# DAC.net
KiCad netlist of a schematic drawn in Altium Designer
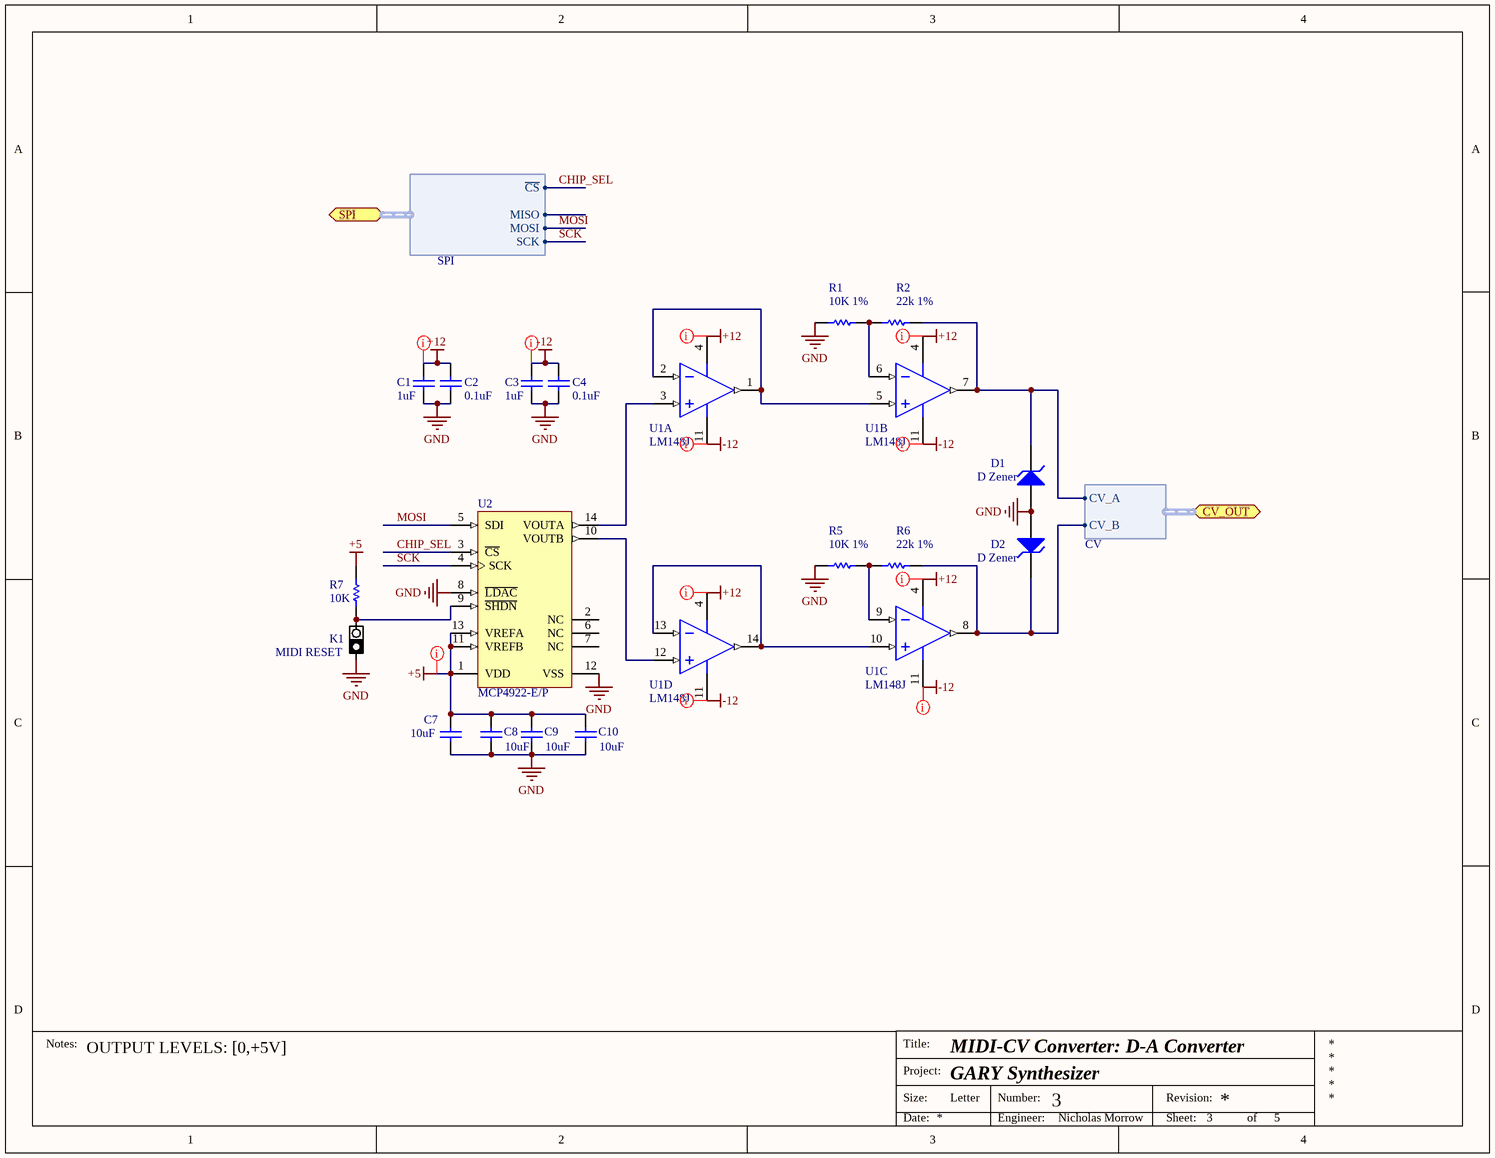
[diagram p0: DAC.SchDoc]

(export (version "E")
  (design (tool "Eeschema 10.0.6"))
  (components
    (comp (ref "C1")
      (value "1uF")
      (footprint "CAP 5X11")
      (description "Capacitor")
      (fields (field (name "Comment") "Cap") (field (name "PUBLISHER") "Altium Limited"))
      (libsource (lib "Miscellaneous Devices") (part "Cap"))
    )
    (comp (ref "C2")
      (value "0.1uF")
      (footprint "CAP 5X11")
      (description "Capacitor")
      (fields (field (name "Comment") "Cap") (field (name "PUBLISHER") "Altium Limited"))
      (libsource (lib "Miscellaneous Devices") (part "Cap"))
    )
    (comp (ref "C3")
      (value "1uF")
      (footprint "CAP 5X11")
      (description "Capacitor")
      (fields (field (name "Comment") "Cap") (field (name "PUBLISHER") "Altium Limited"))
      (libsource (lib "Miscellaneous Devices") (part "Cap"))
    )
    (comp (ref "C4")
      (value "0.1uF")
      (footprint "CAP 5X11")
      (description "Capacitor")
      (fields (field (name "Comment") "Cap") (field (name "PUBLISHER") "Altium Limited"))
      (libsource (lib "Miscellaneous Devices") (part "Cap"))
    )
    (comp (ref "C7")
      (value "10uF")
      (footprint "CAP 5X11")
      (description "Capacitor")
      (fields (field (name "Comment") "Cap") (field (name "PUBLISHER") "Altium Limited"))
      (libsource (lib "Miscellaneous Devices") (part "Cap"))
    )
    (comp (ref "C8")
      (value "10uF")
      (footprint "CAP 5X11")
      (description "Capacitor")
      (fields (field (name "Comment") "Cap") (field (name "PUBLISHER") "Altium Limited"))
      (libsource (lib "Miscellaneous Devices") (part "Cap"))
    )
    (comp (ref "C9")
      (value "10uF")
      (footprint "CAP 5X11")
      (description "Capacitor")
      (fields (field (name "Comment") "Cap") (field (name "PUBLISHER") "Altium Limited"))
      (libsource (lib "Miscellaneous Devices") (part "Cap"))
    )
    (comp (ref "C10")
      (value "10uF")
      (footprint "CAP 5X11")
      (description "Capacitor")
      (fields (field (name "Comment") "Cap") (field (name "PUBLISHER") "Altium Limited"))
      (libsource (lib "Miscellaneous Devices") (part "Cap"))
    )
    (comp (ref "D1")
      (value "D Zener")
      (footprint "DIODE-0.4")
      (description "Zener Diode")
      (fields
        (field (name "MANUFACTURER") "NXP Semiconductors")
        (field (name "MANUFACTURER PART NUMBER") "NZX3V0C,133")
        (field (name "PUBLISHER") "Altium Limited")
      )
      (libsource (lib "Miscellaneous Devices") (part "D Zener"))
    )
    (comp (ref "D2")
      (value "D Zener")
      (footprint "DIODE-0.4")
      (description "Zener Diode")
      (fields
        (field (name "MANUFACTURER") "NXP Semiconductors")
        (field (name "MANUFACTURER PART NUMBER") "NZX3V0C,133")
        (field (name "PUBLISHER") "Altium Limited")
      )
      (libsource (lib "Miscellaneous Devices") (part "D Zener"))
    )
    (comp (ref "K1")
      (value "MIDI RESET")
      (footprint "JMPR2")
      (description "JMPR2 OPEN BY DEFAULT")
      (fields
        (field (name "MANUFACTURER") "Sullins Connector Solutions")
        (field (name "MANUFACTURER PART NUMBER") "PBC36SAAN")
      )
      (libsource (lib "vh_altium_library") (part "JMPR2"))
    )
    (comp (ref "R1")
      (value "10K 1%")
      (footprint "AXIAL-0.3")
      (description "Resistor")
      (fields (field (name "PUBLISHER") "Altium Limited"))
      (libsource (lib "Miscellaneous Devices") (part "Res1"))
    )
    (comp (ref "R2")
      (value "22k 1%")
      (footprint "AXIAL-0.3")
      (description "Resistor")
      (fields (field (name "PUBLISHER") "Altium Limited"))
      (libsource (lib "Miscellaneous Devices") (part "Res1"))
    )
    (comp (ref "R5")
      (value "10K 1%")
      (footprint "AXIAL-0.3")
      (description "Resistor")
      (fields (field (name "PUBLISHER") "Altium Limited"))
      (libsource (lib "Miscellaneous Devices") (part "Res1"))
    )
    (comp (ref "R6")
      (value "22k 1%")
      (footprint "AXIAL-0.3")
      (description "Resistor")
      (fields (field (name "PUBLISHER") "Altium Limited"))
      (libsource (lib "Miscellaneous Devices") (part "Res1"))
    )
    (comp (ref "R7")
      (value "10K")
      (footprint "AXIAL-0.3")
      (description "Resistor")
      (fields (field (name "PUBLISHER") "Altium Limited"))
      (libsource (lib "Miscellaneous Devices") (part "Res1"))
    )
    (comp (ref "U1")
      (value "LM148J")
      (footprint "J14A")
      (description "Series Quad 741 Op Amp, 14-pin CerDIP")
      (fields (field (name "MANUFACTURER") "National Semiconductor"))
      (libsource (lib "National Semiconductor Amplifier") (part "LM148J"))
    )
    (comp (ref "U2")
      (value "MCP4922-E/P")
      (footprint "PDIP300-P14")
      (description "12-Bit DAC with SPI Interface, 14-Pin PDIP, Extended Temperature")
      (fields (field (name "MANUFACTURER") "Microchip"))
      (libsource (lib "Microchip Mixed Signal") (part "MCP4922-E/P"))
    )
  )
  (nets
    (net (code "3") (name "+5") (class "Default")
      (node (ref "C10") (pin "2") (pinfunction "2_2") (pintype "passive"))
      (node (ref "C7") (pin "2") (pinfunction "2_2") (pintype "passive"))
      (node (ref "C8") (pin "2") (pinfunction "2_2") (pintype "passive"))
      (node (ref "C9") (pin "2") (pinfunction "2_2") (pintype "passive"))
      (node (ref "R7") (pin "2") (pinfunction "2_2") (pintype "passive"))
      (node (ref "U2") (pin "1") (pinfunction "VDD_1") (pintype "power_in"))
      (node (ref "U2") (pin "11") (pinfunction "VREFB_11") (pintype "input"))
      (node (ref "U2") (pin "13") (pinfunction "VREFA_13") (pintype "input"))
    )
    (net (code "4") (name "+12") (class "Default")
      (node (ref "C1") (pin "2") (pinfunction "2_2") (pintype "passive"))
      (node (ref "C2") (pin "2") (pinfunction "2_2") (pintype "passive"))
      (node (ref "U1") (pin "4") (pinfunction "V+_4") (pintype "power_in"))
    )
    (net (code "5") (name "-12") (class "Default")
      (node (ref "C3") (pin "2") (pinfunction "2_2") (pintype "passive"))
      (node (ref "C4") (pin "2") (pinfunction "2_2") (pintype "passive"))
      (node (ref "U1") (pin "11") (pinfunction "V-_11") (pintype "power_in"))
    )
    (net (code "6") (name "/CHIP_SEL") (class "Default")
      (node (ref "U2") (pin "3") (pinfunction "~{CS}_3") (pintype "input"))
    )
    (net (code "7") (name "/MOSI") (class "Default")
      (node (ref "U2") (pin "5") (pinfunction "SDI_5") (pintype "input"))
    )
    (net (code "8") (name "/SCK") (class "Default")
      (node (ref "U2") (pin "4") (pinfunction "SCK_4") (pintype "input"))
    )
    (net (code "11") (name "GND") (class "Default")
      (node (ref "C1") (pin "1") (pinfunction "1_1") (pintype "passive"))
      (node (ref "C10") (pin "1") (pinfunction "1_1") (pintype "passive"))
      (node (ref "C2") (pin "1") (pinfunction "1_1") (pintype "passive"))
      (node (ref "C3") (pin "1") (pinfunction "1_1") (pintype "passive"))
      (node (ref "C4") (pin "1") (pinfunction "1_1") (pintype "passive"))
      (node (ref "C7") (pin "1") (pinfunction "1_1") (pintype "passive"))
      (node (ref "C8") (pin "1") (pinfunction "1_1") (pintype "passive"))
      (node (ref "C9") (pin "1") (pinfunction "1_1") (pintype "passive"))
      (node (ref "D1") (pin "1") (pinfunction "A_1") (pintype "passive"))
      (node (ref "D2") (pin "1") (pinfunction "A_1") (pintype "passive"))
      (node (ref "K1") (pin "1") (pintype "passive"))
      (node (ref "R1") (pin "2") (pinfunction "2_2") (pintype "passive"))
      (node (ref "R5") (pin "2") (pinfunction "2_2") (pintype "passive"))
      (node (ref "U2") (pin "12") (pinfunction "VSS_12") (pintype "power_in"))
      (node (ref "U2") (pin "8") (pinfunction "~{LDAC}_8") (pintype "input"))
    )
    (net (code "12") (name "Net-(D1-K)") (class "Default")
      (node (ref "D1") (pin "2") (pinfunction "K_2") (pintype "passive"))
      (node (ref "R2") (pin "1") (pinfunction "1_1") (pintype "passive"))
      (node (ref "U1") (pin "7") (pinfunction "OUT2_7") (pintype "output"))
    )
    (net (code "13") (name "Net-(D2-K)") (class "Default")
      (node (ref "D2") (pin "2") (pinfunction "K_2") (pintype "passive"))
      (node (ref "R6") (pin "1") (pinfunction "1_1") (pintype "passive"))
      (node (ref "U1") (pin "8") (pinfunction "OUT3_8") (pintype "output"))
    )
    (net (code "14") (name "Net-(U1A-IN1+)") (class "Default")
      (node (ref "U1") (pin "3") (pinfunction "IN1+_3") (pintype "input"))
      (node (ref "U2") (pin "14") (pinfunction "VOUTA_14") (pintype "output"))
    )
    (net (code "15") (name "Net-(U1A-IN1-)") (class "Default")
      (node (ref "U1") (pin "1") (pinfunction "OUT1_1") (pintype "output"))
      (node (ref "U1") (pin "2") (pinfunction "IN1-_2") (pintype "input"))
      (node (ref "U1") (pin "5") (pinfunction "IN2+_5") (pintype "input"))
    )
    (net (code "16") (name "Net-(U1B-IN2-)") (class "Default")
      (node (ref "R1") (pin "1") (pinfunction "1_1") (pintype "passive"))
      (node (ref "R2") (pin "2") (pinfunction "2_2") (pintype "passive"))
      (node (ref "U1") (pin "6") (pinfunction "IN2-_6") (pintype "input"))
    )
    (net (code "17") (name "Net-(U1C-IN3+)") (class "Default")
      (node (ref "U1") (pin "10") (pinfunction "IN3+_10") (pintype "input"))
      (node (ref "U1") (pin "13") (pinfunction "IN4-_13") (pintype "input"))
      (node (ref "U1") (pin "14") (pinfunction "OUT4_14") (pintype "output"))
    )
    (net (code "18") (name "Net-(U1C-IN3-)") (class "Default")
      (node (ref "R5") (pin "1") (pinfunction "1_1") (pintype "passive"))
      (node (ref "R6") (pin "2") (pinfunction "2_2") (pintype "passive"))
      (node (ref "U1") (pin "9") (pinfunction "IN3-_9") (pintype "input"))
    )
    (net (code "19") (name "Net-(U1D-IN4+)") (class "Default")
      (node (ref "U1") (pin "12") (pinfunction "IN4+_12") (pintype "input"))
      (node (ref "U2") (pin "10") (pinfunction "VOUTB_10") (pintype "output"))
    )
    (net (code "20") (name "Net-(U2-~{SHDN})") (class "Default")
      (node (ref "K1") (pin "2") (pintype "passive"))
      (node (ref "R7") (pin "1") (pinfunction "1_1") (pintype "passive"))
      (node (ref "U2") (pin "9") (pinfunction "~{SHDN}_9") (pintype "input"))
    )
    (net (code "21") (name "unconnected-(U2-NC-Pad2)") (class "Default")
      (node (ref "U2") (pin "2") (pinfunction "NC_2") (pintype "passive"))
    )
    (net (code "22") (name "unconnected-(U2-NC-Pad6)") (class "Default")
      (node (ref "U2") (pin "6") (pinfunction "NC_6") (pintype "passive"))
    )
    (net (code "23") (name "unconnected-(U2-NC-Pad7)") (class "Default")
      (node (ref "U2") (pin "7") (pinfunction "NC_7") (pintype "passive"))
    )
  )
)
